# KGGRdac.net
KiCad netlist of a schematic drawn in EAGLE
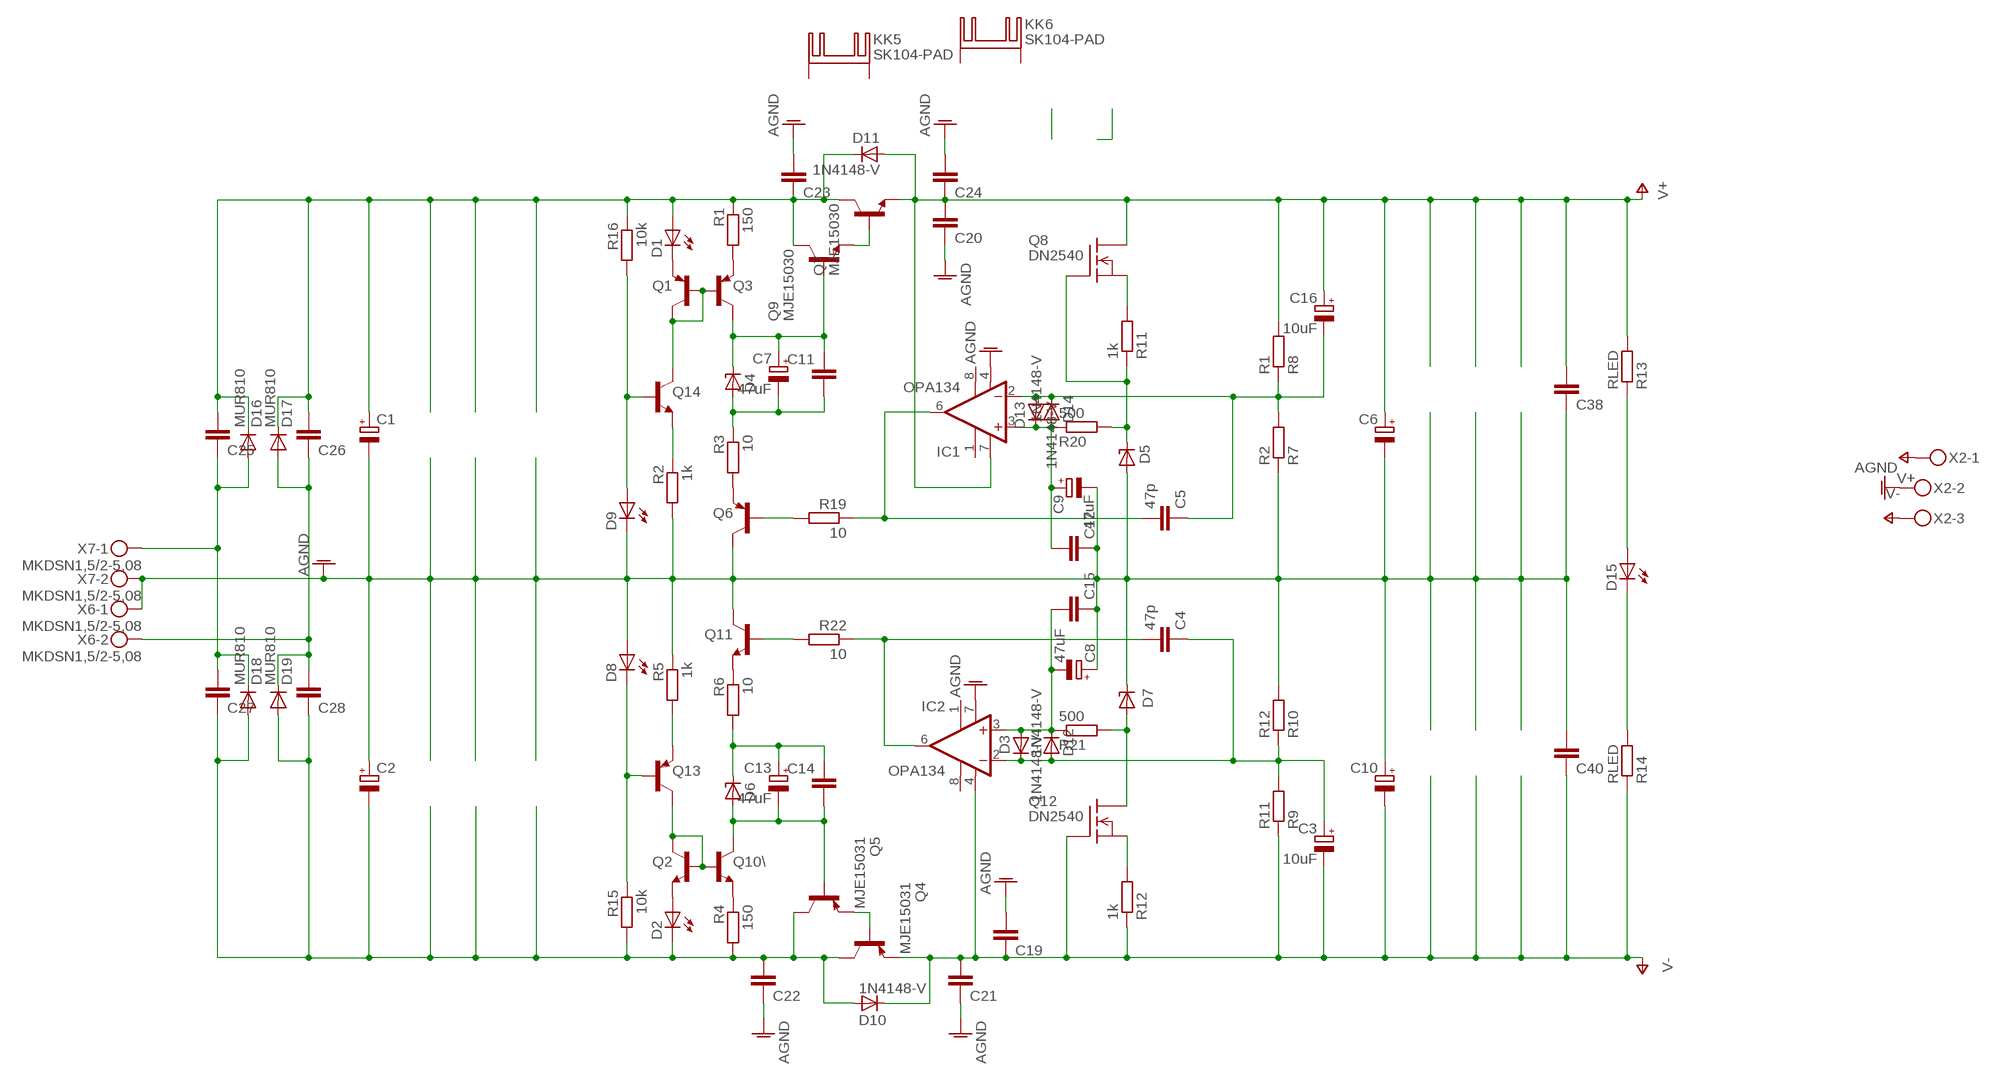
[diagram p0: schematic, sheet 1]
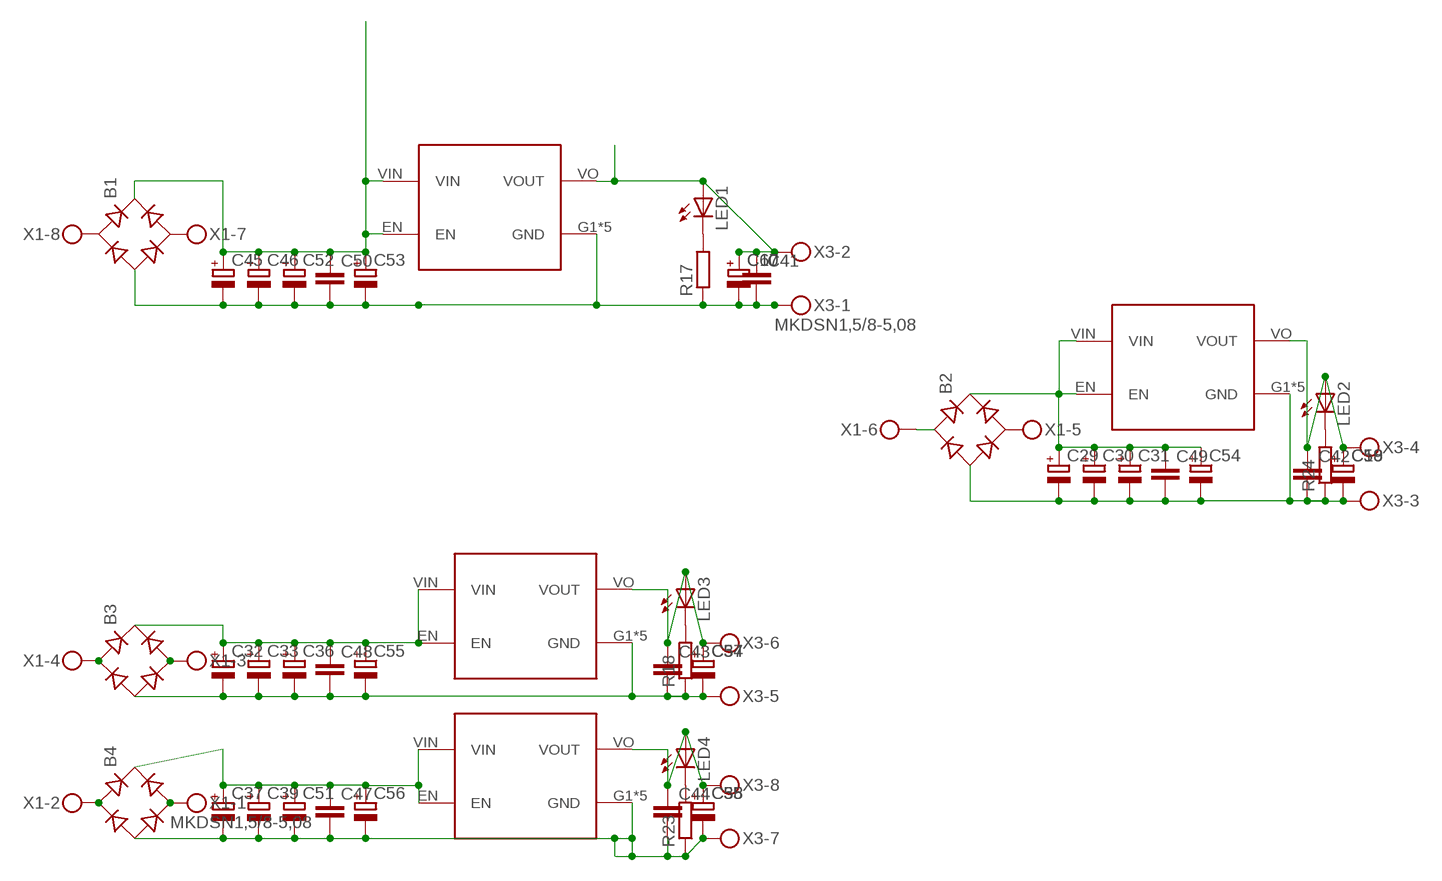
[diagram p1: schematic, sheet 2]
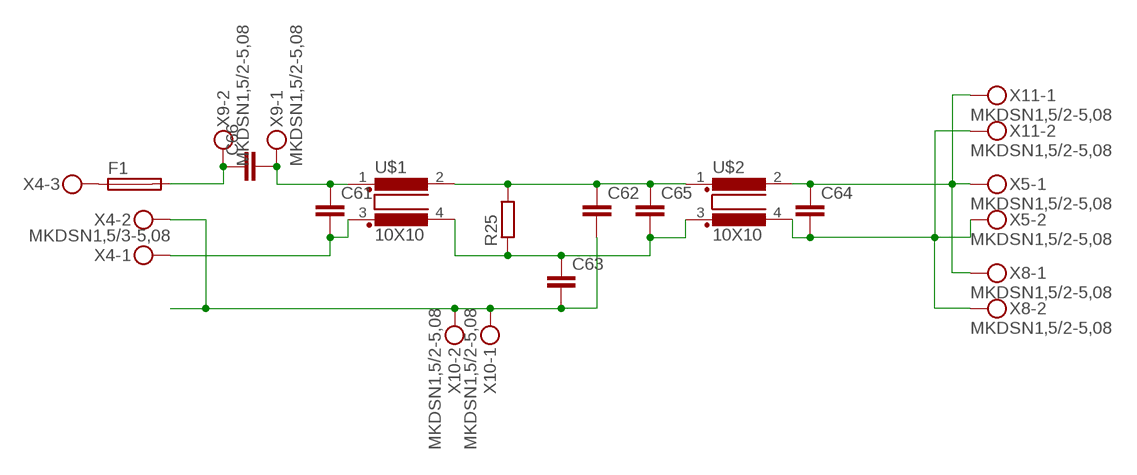
[diagram p2: schematic, sheet 3]

(export (version "E")
  (design (tool "Eeschema 10.0.6"))
  (components
    (comp (ref "C1")
      (value "CPOL-EUE10-35")
      (footprint "eagle-import:EB35D")
      (libsource (lib "eagle-import") (part "CPOL-EUE10-35"))
    )
    (comp (ref "C2")
      (value "CPOL-EUE10-35")
      (footprint "eagle-import:EB35D")
      (libsource (lib "eagle-import") (part "CPOL-EUE10-35"))
    )
    (comp (ref "C3")
      (value "10uF")
      (footprint "eagle-import:SP-CAP-CX")
      (libsource (lib "eagle-import") (part "CPOL-EUSP-CAP-CX"))
    )
    (comp (ref "C4")
      (value "47p")
      (footprint "eagle-import:C1206")
      (libsource (lib "eagle-import") (part "C-EUC1206"))
    )
    (comp (ref "C5")
      (value "47p")
      (footprint "eagle-import:C1206")
      (libsource (lib "eagle-import") (part "C-EUC1206"))
    )
    (comp (ref "C6")
      (value "CPOL-EUE5-13")
      (footprint "eagle-import:E5-13")
      (libsource (lib "eagle-import") (part "CPOL-EUE5-13"))
    )
    (comp (ref "C7")
      (value "47uF")
      (footprint "eagle-import:SP-CAP-CX")
      (libsource (lib "eagle-import") (part "CPOL-EUSP-CAP-CX"))
    )
    (comp (ref "C8")
      (value "47uF")
      (footprint "eagle-import:SP-CAP-CX")
      (libsource (lib "eagle-import") (part "CPOL-EUSP-CAP-CX"))
    )
    (comp (ref "C9")
      (value "47uF")
      (footprint "eagle-import:SP-CAP-CX")
      (libsource (lib "eagle-import") (part "CPOL-EUSP-CAP-CX"))
    )
    (comp (ref "C10")
      (value "CPOL-EUE5-13")
      (footprint "eagle-import:E5-13")
      (libsource (lib "eagle-import") (part "CPOL-EUE5-13"))
    )
    (comp (ref "C11")
      (value "C-EUC1206")
      (footprint "eagle-import:C1206")
      (libsource (lib "eagle-import") (part "C-EUC1206"))
    )
    (comp (ref "C12")
      (value "C-EU050-035X075")
      (footprint "eagle-import:C050-035X075")
      (libsource (lib "eagle-import") (part "C-EU050-035X075"))
    )
    (comp (ref "C13")
      (value "47uF")
      (footprint "eagle-import:SP-CAP-CX")
      (libsource (lib "eagle-import") (part "CPOL-EUSP-CAP-CX"))
    )
    (comp (ref "C14")
      (value "C-EUC1206")
      (footprint "eagle-import:C1206")
      (libsource (lib "eagle-import") (part "C-EUC1206"))
    )
    (comp (ref "C15")
      (value "C-EU050-035X075")
      (footprint "eagle-import:C050-035X075")
      (libsource (lib "eagle-import") (part "C-EU050-035X075"))
    )
    (comp (ref "C16")
      (value "10uF")
      (footprint "eagle-import:SP-CAP-CX")
      (libsource (lib "eagle-import") (part "CPOL-EUSP-CAP-CX"))
    )
    (comp (ref "C19")
      (value "C-EU050-035X075")
      (footprint "eagle-import:C050-035X075")
      (libsource (lib "eagle-import") (part "C-EU050-035X075"))
    )
    (comp (ref "C20")
      (value "C-EU050-035X075")
      (footprint "eagle-import:C050-035X075")
      (libsource (lib "eagle-import") (part "C-EU050-035X075"))
    )
    (comp (ref "C21")
      (value "C-EU050-035X075")
      (footprint "eagle-import:C050-035X075")
      (libsource (lib "eagle-import") (part "C-EU050-035X075"))
    )
    (comp (ref "C22")
      (value "C-EU050-075X075")
      (footprint "eagle-import:C050-075X075")
      (libsource (lib "eagle-import") (part "C-EU050-075X075"))
    )
    (comp (ref "C23")
      (value "C-EU050-075X075")
      (footprint "eagle-import:C050-075X075")
      (libsource (lib "eagle-import") (part "C-EU050-075X075"))
    )
    (comp (ref "C24")
      (value "C-EU050-035X075")
      (footprint "eagle-import:C050-035X075")
      (libsource (lib "eagle-import") (part "C-EU050-035X075"))
    )
    (comp (ref "C25")
      (value "C-EU050-035X075")
      (footprint "eagle-import:C050-035X075")
      (libsource (lib "eagle-import") (part "C-EU050-035X075"))
    )
    (comp (ref "C26")
      (value "C-EU050-035X075")
      (footprint "eagle-import:C050-035X075")
      (libsource (lib "eagle-import") (part "C-EU050-035X075"))
    )
    (comp (ref "C27")
      (value "C-EU050-035X075")
      (footprint "eagle-import:C050-035X075")
      (libsource (lib "eagle-import") (part "C-EU050-035X075"))
    )
    (comp (ref "C28")
      (value "C-EU050-035X075")
      (footprint "eagle-import:C050-035X075")
      (libsource (lib "eagle-import") (part "C-EU050-035X075"))
    )
    (comp (ref "C38")
      (value "C-EU050-035X075")
      (footprint "eagle-import:C050-035X075")
      (libsource (lib "eagle-import") (part "C-EU050-035X075"))
    )
    (comp (ref "C40")
      (value "C-EU050-035X075")
      (footprint "eagle-import:C050-035X075")
      (libsource (lib "eagle-import") (part "C-EU050-035X075"))
    )
    (comp (ref "D1")
      (value "LED5MM")
      (footprint "eagle-import:LED5MM")
      (libsource (lib "eagle-import") (part "LED5MM"))
    )
    (comp (ref "D2")
      (value "LED5MM")
      (footprint "eagle-import:LED5MM")
      (libsource (lib "eagle-import") (part "LED5MM"))
    )
    (comp (ref "D3")
      (value "1N4148-V")
      (footprint "eagle-import:1N4148")
      (libsource (lib "eagle-import") (part "1N4148-V"))
    )
    (comp (ref "D4")
      (value "1N4728")
      (footprint "eagle-import:DO41Z10")
      (libsource (lib "eagle-import") (part "1N4728"))
    )
    (comp (ref "D5")
      (value "LT1021")
      (footprint "eagle-import:DIL08")
      (libsource (lib "eagle-import") (part "LT1021-V"))
    )
    (comp (ref "D6")
      (value "1N4728")
      (footprint "eagle-import:DO41Z10")
      (libsource (lib "eagle-import") (part "1N4728"))
    )
    (comp (ref "D7")
      (value "LT1021")
      (footprint "eagle-import:DIL08")
      (libsource (lib "eagle-import") (part "LT1021-V"))
    )
    (comp (ref "D8")
      (value "LED5MM")
      (footprint "eagle-import:LED5MM")
      (libsource (lib "eagle-import") (part "LED5MM"))
    )
    (comp (ref "D9")
      (value "LED5MM")
      (footprint "eagle-import:LED5MM")
      (libsource (lib "eagle-import") (part "LED5MM"))
    )
    (comp (ref "D10")
      (value "1N4148-V")
      (footprint "eagle-import:1N4148")
      (libsource (lib "eagle-import") (part "1N4148-V"))
    )
    (comp (ref "D11")
      (value "1N4148-V")
      (footprint "eagle-import:1N4148")
      (libsource (lib "eagle-import") (part "1N4148-V"))
    )
    (comp (ref "D12")
      (value "1N4148-V")
      (footprint "eagle-import:1N4148")
      (libsource (lib "eagle-import") (part "1N4148-V"))
    )
    (comp (ref "D13")
      (value "1N4148-V")
      (footprint "eagle-import:1N4148")
      (libsource (lib "eagle-import") (part "1N4148-V"))
    )
    (comp (ref "D14")
      (value "1N4148-V")
      (footprint "eagle-import:1N4148")
      (libsource (lib "eagle-import") (part "1N4148-V"))
    )
    (comp (ref "D15")
      (value "LED5MM")
      (footprint "eagle-import:LED5MM")
      (libsource (lib "eagle-import") (part "LED5MM"))
    )
    (comp (ref "D16")
      (value "MUR810")
      (footprint "eagle-import:TO220ACS")
      (libsource (lib "eagle-import") (part "MUR810"))
    )
    (comp (ref "D17")
      (value "MUR810")
      (footprint "eagle-import:TO220ACS")
      (libsource (lib "eagle-import") (part "MUR810"))
    )
    (comp (ref "D18")
      (value "MUR810")
      (footprint "eagle-import:TO220ACS")
      (libsource (lib "eagle-import") (part "MUR810"))
    )
    (comp (ref "D19")
      (value "MUR810")
      (footprint "eagle-import:TO220ACS")
      (libsource (lib "eagle-import") (part "MUR810"))
    )
    (comp (ref "IC1")
      (value "OPA134")
      (footprint "eagle-import:DIL08")
      (fields (field (name "MF") "TEXAS INSTRUMENTS") (field (name "MPN") "OPA134PA"))
      (libsource (lib "eagle-import") (part "OPA134P"))
    )
    (comp (ref "IC2")
      (value "OPA134")
      (footprint "eagle-import:DIL08")
      (fields (field (name "MF") "TEXAS INSTRUMENTS") (field (name "MPN") "OPA134PA"))
      (libsource (lib "eagle-import") (part "OPA134P"))
    )
    (comp (ref "KK5")
      (value "SK104-PAD")
      (footprint "eagle-import:SK104-PAD")
      (libsource (lib "eagle-import") (part "SK104-PAD"))
    )
    (comp (ref "KK6")
      (value "SK104-PAD")
      (footprint "eagle-import:SK104-PAD")
      (libsource (lib "eagle-import") (part "SK104-PAD"))
    )
    (comp (ref "Q1")
      (value "MPSA92-PNP-TO92-EBC")
      (footprint "eagle-import:TO92-EBC")
      (libsource (lib "eagle-import") (part "-PNP-TO92-EBCMPSA92"))
    )
    (comp (ref "Q2")
      (value "MPSA42-NPN-TO92-EBC")
      (footprint "eagle-import:TO92-EBC")
      (libsource (lib "eagle-import") (part "-NPN-TO92-EBCMPSA42"))
    )
    (comp (ref "Q3")
      (value "MPSA92-PNP-TO92-EBC")
      (footprint "eagle-import:TO92-EBC")
      (libsource (lib "eagle-import") (part "-PNP-TO92-EBCMPSA92"))
    )
    (comp (ref "Q4")
      (value "MJE15031")
      (footprint "eagle-import:TO220KG")
      (libsource (lib "eagle-import") (part "MJE15031"))
    )
    (comp (ref "Q5")
      (value "MJE15031")
      (footprint "eagle-import:TO220KG")
      (libsource (lib "eagle-import") (part "MJE15031"))
    )
    (comp (ref "Q6")
      (value "MPSA92-PNP-TO92-EBC")
      (footprint "eagle-import:TO92-EBC")
      (libsource (lib "eagle-import") (part "-PNP-TO92-EBCMPSA92"))
    )
    (comp (ref "Q7")
      (value "MJE15030")
      (footprint "eagle-import:TO220KG")
      (libsource (lib "eagle-import") (part "MJE15030"))
    )
    (comp (ref "Q8")
      (value "DN2540")
      (footprint "eagle-import:TO92-")
      (libsource (lib "eagle-import") (part "2N7000TO92"))
    )
    (comp (ref "Q9")
      (value "MJE15030")
      (footprint "eagle-import:TO220KG")
      (libsource (lib "eagle-import") (part "MJE15030"))
    )
    (comp (ref "Q10\\")
      (value "MPSA42-NPN-TO92-EBC")
      (footprint "eagle-import:TO92-EBC")
      (libsource (lib "eagle-import") (part "-NPN-TO92-EBCMPSA42"))
    )
    (comp (ref "Q11")
      (value "MPSA42-NPN-TO92-EBC")
      (footprint "eagle-import:TO92-EBC")
      (libsource (lib "eagle-import") (part "-NPN-TO92-EBCMPSA42"))
    )
    (comp (ref "Q12")
      (value "DN2540")
      (footprint "eagle-import:TO92-")
      (libsource (lib "eagle-import") (part "2N7000TO92"))
    )
    (comp (ref "Q13")
      (value "MPSA92-PNP-TO92-EBC")
      (footprint "eagle-import:TO92-EBC")
      (libsource (lib "eagle-import") (part "-PNP-TO92-EBCMPSA92"))
    )
    (comp (ref "Q14")
      (value "MPSA42-NPN-TO92-EBC")
      (footprint "eagle-import:TO92-EBC")
      (libsource (lib "eagle-import") (part "-NPN-TO92-EBCMPSA42"))
    )
    (comp (ref "R1")
      (value "150")
      (footprint "eagle-import:0207_2V")
      (libsource (lib "eagle-import") (part "R-EU_0207/2V"))
    )
    (comp (ref "R2")
      (value "1k")
      (footprint "eagle-import:0207_2V")
      (libsource (lib "eagle-import") (part "R-EU_0207/2V"))
    )
    (comp (ref "R3")
      (value "10")
      (footprint "eagle-import:0207_2V")
      (libsource (lib "eagle-import") (part "R-EU_0207/2V"))
    )
    (comp (ref "R4")
      (value "150")
      (footprint "eagle-import:0207_2V")
      (libsource (lib "eagle-import") (part "R-EU_0207/2V"))
    )
    (comp (ref "R5")
      (value "1k")
      (footprint "eagle-import:0207_2V")
      (libsource (lib "eagle-import") (part "R-EU_0207/2V"))
    )
    (comp (ref "R6")
      (value "10")
      (footprint "eagle-import:0207_2V")
      (libsource (lib "eagle-import") (part "R-EU_0207/2V"))
    )
    (comp (ref "R7")
      (value "R2")
      (footprint "eagle-import:0207_2V")
      (libsource (lib "eagle-import") (part "R-EU_0207/2V"))
    )
    (comp (ref "R8")
      (value "R1")
      (footprint "eagle-import:0207_2V")
      (libsource (lib "eagle-import") (part "R-EU_0207/2V"))
    )
    (comp (ref "R9")
      (value "R11")
      (footprint "eagle-import:0207_2V")
      (libsource (lib "eagle-import") (part "R-EU_0207/2V"))
    )
    (comp (ref "R10")
      (value "R12")
      (footprint "eagle-import:0207_2V")
      (libsource (lib "eagle-import") (part "R-EU_0207/2V"))
    )
    (comp (ref "R11")
      (value "1k")
      (footprint "eagle-import:0207_2V")
      (libsource (lib "eagle-import") (part "R-EU_0207/2V"))
    )
    (comp (ref "R12")
      (value "1k")
      (footprint "eagle-import:0207_2V")
      (libsource (lib "eagle-import") (part "R-EU_0207/2V"))
    )
    (comp (ref "R13")
      (value "RLED")
      (footprint "eagle-import:0207_2V")
      (libsource (lib "eagle-import") (part "R-EU_0207/2V"))
    )
    (comp (ref "R14")
      (value "RLED")
      (footprint "eagle-import:0207_2V")
      (libsource (lib "eagle-import") (part "R-EU_0207/2V"))
    )
    (comp (ref "R15")
      (value "10k")
      (footprint "eagle-import:0207_2V")
      (libsource (lib "eagle-import") (part "R-EU_0207/2V"))
    )
    (comp (ref "R16")
      (value "10k")
      (footprint "eagle-import:0207_2V")
      (libsource (lib "eagle-import") (part "R-EU_0207/2V"))
    )
    (comp (ref "R19")
      (value "10")
      (footprint "eagle-import:0207_2V")
      (libsource (lib "eagle-import") (part "R-EU_0207/2V"))
    )
    (comp (ref "R20")
      (value "500")
      (footprint "eagle-import:0207_2V")
      (libsource (lib "eagle-import") (part "R-EU_0207/2V"))
    )
    (comp (ref "R21")
      (value "500")
      (footprint "eagle-import:0207_2V")
      (libsource (lib "eagle-import") (part "R-EU_0207/2V"))
    )
    (comp (ref "R22")
      (value "10")
      (footprint "eagle-import:0207_2V")
      (libsource (lib "eagle-import") (part "R-EU_0207/2V"))
    )
    (comp (ref "X2")
      (value "MKDSN1,5/3-5,08")
      (footprint "eagle-import:MKDSN1,5_3-5,08")
      (libsource (lib "eagle-import") (part "MKDSN1,5/3-5,08"))
    )
    (comp (ref "X6")
      (value "MKDSN1,5/2-5,08")
      (footprint "eagle-import:MKDSN1,5_2-5,08")
      (libsource (lib "eagle-import") (part "MKDSN1,5/2-5,08"))
    )
    (comp (ref "X7")
      (value "MKDSN1,5/2-5,08")
      (footprint "eagle-import:MKDSN1,5_2-5,08")
      (libsource (lib "eagle-import") (part "MKDSN1,5/2-5,08"))
    )
    (comp (ref "B1")
      (value "RB1A")
      (footprint "eagle-import:RB1A")
      (libsource (lib "eagle-import") (part "RB1A"))
    )
    (comp (ref "B2")
      (value "RB1A")
      (footprint "eagle-import:RB1A")
      (libsource (lib "eagle-import") (part "RB1A"))
    )
    (comp (ref "B3")
      (value "RB1A")
      (footprint "eagle-import:RB1A")
      (libsource (lib "eagle-import") (part "RB1A"))
    )
    (comp (ref "B4")
      (value "RB1A")
      (footprint "eagle-import:RB1A")
      (libsource (lib "eagle-import") (part "RB1A"))
    )
    (comp (ref "C17")
      (value "CPOL-EUSP-CAP-CX")
      (footprint "eagle-import:SP-CAP-CX")
      (libsource (lib "eagle-import") (part "CPOL-EUSP-CAP-CX"))
    )
    (comp (ref "C18")
      (value "CPOL-EUSP-CAP-CX")
      (footprint "eagle-import:SP-CAP-CX")
      (libsource (lib "eagle-import") (part "CPOL-EUSP-CAP-CX"))
    )
    (comp (ref "C29")
      (value "CPOL-EUSP-CAP-CX")
      (footprint "eagle-import:SP-CAP-CX")
      (libsource (lib "eagle-import") (part "CPOL-EUSP-CAP-CX"))
    )
    (comp (ref "C30")
      (value "CPOL-EUSP-CAP-CX")
      (footprint "eagle-import:SP-CAP-CX")
      (libsource (lib "eagle-import") (part "CPOL-EUSP-CAP-CX"))
    )
    (comp (ref "C31")
      (value "CPOL-EUSP-CAP-CX")
      (footprint "eagle-import:SP-CAP-CX")
      (libsource (lib "eagle-import") (part "CPOL-EUSP-CAP-CX"))
    )
    (comp (ref "C32")
      (value "CPOL-EUSP-CAP-CX")
      (footprint "eagle-import:SP-CAP-CX")
      (libsource (lib "eagle-import") (part "CPOL-EUSP-CAP-CX"))
    )
    (comp (ref "C33")
      (value "CPOL-EUSP-CAP-CX")
      (footprint "eagle-import:SP-CAP-CX")
      (libsource (lib "eagle-import") (part "CPOL-EUSP-CAP-CX"))
    )
    (comp (ref "C34")
      (value "CPOL-EUSP-CAP-CX")
      (footprint "eagle-import:SP-CAP-CX")
      (libsource (lib "eagle-import") (part "CPOL-EUSP-CAP-CX"))
    )
    (comp (ref "C35")
      (value "CPOL-EUSP-CAP-CX")
      (footprint "eagle-import:SP-CAP-CX")
      (libsource (lib "eagle-import") (part "CPOL-EUSP-CAP-CX"))
    )
    (comp (ref "C36")
      (value "CPOL-EUSP-CAP-CX")
      (footprint "eagle-import:SP-CAP-CX")
      (libsource (lib "eagle-import") (part "CPOL-EUSP-CAP-CX"))
    )
    (comp (ref "C37")
      (value "CPOL-EUSP-CAP-CX")
      (footprint "eagle-import:SP-CAP-CX")
      (libsource (lib "eagle-import") (part "CPOL-EUSP-CAP-CX"))
    )
    (comp (ref "C39")
      (value "CPOL-EUSP-CAP-CX")
      (footprint "eagle-import:SP-CAP-CX")
      (libsource (lib "eagle-import") (part "CPOL-EUSP-CAP-CX"))
    )
    (comp (ref "C41")
      (value "C-EUC1206")
      (footprint "eagle-import:C1206")
      (libsource (lib "eagle-import") (part "C-EUC1206"))
    )
    (comp (ref "C42")
      (value "C-EUC1206")
      (footprint "eagle-import:C1206")
      (libsource (lib "eagle-import") (part "C-EUC1206"))
    )
    (comp (ref "C43")
      (value "C-EUC1206")
      (footprint "eagle-import:C1206")
      (libsource (lib "eagle-import") (part "C-EUC1206"))
    )
    (comp (ref "C44")
      (value "C-EUC1206")
      (footprint "eagle-import:C1206")
      (libsource (lib "eagle-import") (part "C-EUC1206"))
    )
    (comp (ref "C45")
      (value "CPOL-EUSP-CAP-CX")
      (footprint "eagle-import:SP-CAP-CX")
      (libsource (lib "eagle-import") (part "CPOL-EUSP-CAP-CX"))
    )
    (comp (ref "C46")
      (value "CPOL-EUSP-CAP-CX")
      (footprint "eagle-import:SP-CAP-CX")
      (libsource (lib "eagle-import") (part "CPOL-EUSP-CAP-CX"))
    )
    (comp (ref "C47")
      (value "C-EUC1206")
      (footprint "eagle-import:C1206")
      (libsource (lib "eagle-import") (part "C-EUC1206"))
    )
    (comp (ref "C48")
      (value "C-EUC1206")
      (footprint "eagle-import:C1206")
      (libsource (lib "eagle-import") (part "C-EUC1206"))
    )
    (comp (ref "C49")
      (value "C-EUC1206")
      (footprint "eagle-import:C1206")
      (libsource (lib "eagle-import") (part "C-EUC1206"))
    )
    (comp (ref "C50")
      (value "C-EUC1206")
      (footprint "eagle-import:C1206")
      (libsource (lib "eagle-import") (part "C-EUC1206"))
    )
    (comp (ref "C51")
      (value "CPOL-EUSP-CAP-CX")
      (footprint "eagle-import:SP-CAP-CX")
      (libsource (lib "eagle-import") (part "CPOL-EUSP-CAP-CX"))
    )
    (comp (ref "C52")
      (value "CPOL-EUSP-CAP-CX")
      (footprint "eagle-import:SP-CAP-CX")
      (libsource (lib "eagle-import") (part "CPOL-EUSP-CAP-CX"))
    )
    (comp (ref "C53")
      (value "CPOL-EUSP-CAP-CX")
      (footprint "eagle-import:SP-CAP-CX")
      (libsource (lib "eagle-import") (part "CPOL-EUSP-CAP-CX"))
    )
    (comp (ref "C54")
      (value "CPOL-EUSP-CAP-CX")
      (footprint "eagle-import:SP-CAP-CX")
      (libsource (lib "eagle-import") (part "CPOL-EUSP-CAP-CX"))
    )
    (comp (ref "C55")
      (value "CPOL-EUSP-CAP-CX")
      (footprint "eagle-import:SP-CAP-CX")
      (libsource (lib "eagle-import") (part "CPOL-EUSP-CAP-CX"))
    )
    (comp (ref "C56")
      (value "CPOL-EUSP-CAP-CX")
      (footprint "eagle-import:SP-CAP-CX")
      (libsource (lib "eagle-import") (part "CPOL-EUSP-CAP-CX"))
    )
    (comp (ref "C57")
      (value "CPOL-EUSP-CAP-CX")
      (footprint "eagle-import:SP-CAP-CX")
      (libsource (lib "eagle-import") (part "CPOL-EUSP-CAP-CX"))
    )
    (comp (ref "C58")
      (value "CPOL-EUSP-CAP-CX")
      (footprint "eagle-import:SP-CAP-CX")
      (libsource (lib "eagle-import") (part "CPOL-EUSP-CAP-CX"))
    )
    (comp (ref "C59")
      (value "CPOL-EUSP-CAP-CX")
      (footprint "eagle-import:SP-CAP-CX")
      (libsource (lib "eagle-import") (part "CPOL-EUSP-CAP-CX"))
    )
    (comp (ref "C60")
      (value "CPOL-EUSP-CAP-CX")
      (footprint "eagle-import:SP-CAP-CX")
      (libsource (lib "eagle-import") (part "CPOL-EUSP-CAP-CX"))
    )
    (comp (ref "LED1")
      (value "LEDSML0805")
      (footprint "eagle-import:SML0805")
      (libsource (lib "eagle-import") (part "LEDSML0805"))
    )
    (comp (ref "LED2")
      (value "LEDSML0805")
      (footprint "eagle-import:SML0805")
      (libsource (lib "eagle-import") (part "LEDSML0805"))
    )
    (comp (ref "LED3")
      (value "LEDSML0805")
      (footprint "eagle-import:SML0805")
      (libsource (lib "eagle-import") (part "LEDSML0805"))
    )
    (comp (ref "LED4")
      (value "LEDSML0805")
      (footprint "eagle-import:SML0805")
      (libsource (lib "eagle-import") (part "LEDSML0805"))
    )
    (comp (ref "R17")
      (value "R-EU_MELF0204W")
      (footprint "eagle-import:MINI_MELF-0204W")
      (libsource (lib "eagle-import") (part "R-EU_MELF0204W"))
    )
    (comp (ref "R18")
      (value "R-EU_MELF0204W")
      (footprint "eagle-import:MINI_MELF-0204W")
      (libsource (lib "eagle-import") (part "R-EU_MELF0204W"))
    )
    (comp (ref "R23")
      (value "R-EU_MELF0204W")
      (footprint "eagle-import:MINI_MELF-0204W")
      (libsource (lib "eagle-import") (part "R-EU_MELF0204W"))
    )
    (comp (ref "R24")
      (value "R-EU_MELF0204W")
      (footprint "eagle-import:MINI_MELF-0204W")
      (libsource (lib "eagle-import") (part "R-EU_MELF0204W"))
    )
    (comp (ref "U$3")
      (value "POWER-MO")
      (footprint "eagle-import:POWER-MO")
      (libsource (lib "eagle-import") (part "POWER-MO"))
    )
    (comp (ref "U$4")
      (value "POWER-MO")
      (footprint "eagle-import:POWER-MO")
      (libsource (lib "eagle-import") (part "POWER-MO"))
    )
    (comp (ref "U$5")
      (value "POWER-MO")
      (footprint "eagle-import:POWER-MO")
      (libsource (lib "eagle-import") (part "POWER-MO"))
    )
    (comp (ref "U$6")
      (value "POWER-MO")
      (footprint "eagle-import:POWER-MO")
      (libsource (lib "eagle-import") (part "POWER-MO"))
    )
    (comp (ref "X1")
      (value "MKDSN1,5/8-5,08")
      (footprint "eagle-import:MKDSN1,5_8-5,08")
      (libsource (lib "eagle-import") (part "MKDSN1,5/8-5,08"))
    )
    (comp (ref "X3")
      (value "MKDSN1,5/8-5,08")
      (footprint "eagle-import:MKDSN1,5_8-5,08")
      (libsource (lib "eagle-import") (part "MKDSN1,5/8-5,08"))
    )
    (comp (ref "C61")
      (value "C-EU225-087X268")
      (footprint "eagle-import:C225-087X268")
      (libsource (lib "eagle-import") (part "C-EU225-087X268"))
    )
    (comp (ref "C62")
      (value "C-EU102-054X133")
      (footprint "eagle-import:C102-054X133")
      (libsource (lib "eagle-import") (part "C-EU102-054X133"))
    )
    (comp (ref "C63")
      (value "C-EU102-054X133")
      (footprint "eagle-import:C102-054X133")
      (libsource (lib "eagle-import") (part "C-EU102-054X133"))
    )
    (comp (ref "C64")
      (value "C-EU225-087X268")
      (footprint "eagle-import:C225-087X268")
      (libsource (lib "eagle-import") (part "C-EU225-087X268"))
    )
    (comp (ref "C65")
      (value "C-EU225-087X268")
      (footprint "eagle-import:C225-087X268")
      (libsource (lib "eagle-import") (part "C-EU225-087X268"))
    )
    (comp (ref "C66")
      (value "C-EU075-042X103")
      (footprint "eagle-import:C075-042X103")
      (libsource (lib "eagle-import") (part "C-EU075-042X103"))
    )
    (comp (ref "F1")
      (value "SH22,5A")
      (footprint "eagle-import:SH22,5A")
      (fields (field (name "MPN") "0031.7701.11"))
      (libsource (lib "eagle-import") (part "SH22,5A"))
    )
    (comp (ref "R25")
      (value "R-EU_0411/15")
      (footprint "eagle-import:0411_15")
      (libsource (lib "eagle-import") (part "R-EU_0411/15"))
    )
    (comp (ref "U$1")
      (value "10X10")
      (footprint "eagle-import:10X10")
      (libsource (lib "eagle-import") (part "10X10"))
    )
    (comp (ref "U$2")
      (value "10X10")
      (footprint "eagle-import:10X10")
      (libsource (lib "eagle-import") (part "10X10"))
    )
    (comp (ref "X4")
      (value "MKDSN1,5/3-5,08")
      (footprint "eagle-import:MKDSN1,5_3-5,08")
      (libsource (lib "eagle-import") (part "MKDSN1,5/3-5,08"))
    )
    (comp (ref "X5")
      (value "MKDSN1,5/2-5,08")
      (footprint "eagle-import:MKDSN1,5_2-5,08")
      (libsource (lib "eagle-import") (part "MKDSN1,5/2-5,08"))
    )
    (comp (ref "X8")
      (value "MKDSN1,5/2-5,08")
      (footprint "eagle-import:MKDSN1,5_2-5,08")
      (libsource (lib "eagle-import") (part "MKDSN1,5/2-5,08"))
    )
    (comp (ref "X9")
      (value "MKDSN1,5/2-5,08")
      (footprint "eagle-import:MKDSN1,5_2-5,08")
      (libsource (lib "eagle-import") (part "MKDSN1,5/2-5,08"))
    )
    (comp (ref "X10")
      (value "MKDSN1,5/2-5,08")
      (footprint "eagle-import:MKDSN1,5_2-5,08")
      (libsource (lib "eagle-import") (part "MKDSN1,5/2-5,08"))
    )
    (comp (ref "X11")
      (value "MKDSN1,5/2-5,08")
      (footprint "eagle-import:MKDSN1,5_2-5,08")
      (libsource (lib "eagle-import") (part "MKDSN1,5/2-5,08"))
    )
  )
  (nets
    (net (code "1") (name "AGND") (class "Default")
      (node (ref "C1") (pin "-") (pinfunction "-_-") (pintype "passive"))
      (node (ref "C10") (pin "+") (pinfunction "+_+") (pintype "passive"))
      (node (ref "C12") (pin "1") (pinfunction "1_1") (pintype "passive"))
      (node (ref "C15") (pin "1") (pinfunction "1_1") (pintype "passive"))
      (node (ref "C19") (pin "2") (pinfunction "2_2") (pintype "passive"))
      (node (ref "C2") (pin "+") (pinfunction "+_+") (pintype "passive"))
      (node (ref "C20") (pin "1") (pinfunction "1_1") (pintype "passive"))
      (node (ref "C21") (pin "1") (pinfunction "1_1") (pintype "passive"))
      (node (ref "C22") (pin "1") (pinfunction "1_1") (pintype "passive"))
      (node (ref "C23") (pin "2") (pinfunction "2_2") (pintype "passive"))
      (node (ref "C24") (pin "2") (pinfunction "2_2") (pintype "passive"))
      (node (ref "C38") (pin "1") (pinfunction "1_1") (pintype "passive"))
      (node (ref "C40") (pin "2") (pinfunction "2_2") (pintype "passive"))
      (node (ref "C6") (pin "-") (pinfunction "-_-") (pintype "passive"))
      (node (ref "C8") (pin "+") (pinfunction "+_+") (pintype "passive"))
      (node (ref "C9") (pin "-") (pinfunction "-_-") (pintype "passive"))
      (node (ref "D5") (pin "4") (pinfunction "GND_4") (pintype "passive"))
      (node (ref "D7") (pin "6") (pinfunction "OUT_6") (pintype "passive"))
      (node (ref "D8") (pin "A") (pinfunction "A_A") (pintype "passive"))
      (node (ref "D9") (pin "K") (pinfunction "C_K") (pintype "passive"))
      (node (ref "IC1") (pin "4") (pinfunction "V-_4") (pintype "power_in"))
      (node (ref "IC2") (pin "7") (pinfunction "V+_7") (pintype "power_in"))
      (node (ref "Q11") (pin "C") (pinfunction "C_C") (pintype "passive"))
      (node (ref "Q6") (pin "C") (pinfunction "C_C") (pintype "passive"))
      (node (ref "R10") (pin "2") (pinfunction "2_2") (pintype "passive"))
      (node (ref "R2") (pin "2") (pinfunction "2_2") (pintype "passive"))
      (node (ref "R5") (pin "1") (pinfunction "1_1") (pintype "passive"))
      (node (ref "R7") (pin "1") (pinfunction "1_1") (pintype "passive"))
      (node (ref "X2") (pin "2") (pinfunction "KL_2") (pintype "passive"))
      (node (ref "X6") (pin "1") (pinfunction "KL_1") (pintype "passive"))
      (node (ref "X7") (pin "2") (pinfunction "KL_2") (pintype "passive"))
    )
    (net (code "2") (name "Net-(B1-Pad+)") (class "Default")
      (node (ref "B1") (pin "+") (pinfunction "+_+") (pintype "passive"))
      (node (ref "C45") (pin "+") (pinfunction "+_+") (pintype "passive"))
      (node (ref "C46") (pin "+") (pinfunction "+_+") (pintype "passive"))
      (node (ref "C50") (pin "1") (pinfunction "1_1") (pintype "passive"))
      (node (ref "C52") (pin "+") (pinfunction "+_+") (pintype "passive"))
      (node (ref "C53") (pin "+") (pinfunction "+_+") (pintype "passive"))
      (node (ref "U$4") (pin "EN") (pinfunction "EN_EN") (pintype "bidirectional"))
      (node (ref "U$4") (pin "VIN") (pinfunction "VIN_VIN") (pintype "bidirectional"))
    )
    (net (code "3") (name "Net-(B2-Pad+)") (class "Default")
      (node (ref "B2") (pin "+") (pinfunction "+_+") (pintype "passive"))
      (node (ref "C29") (pin "+") (pinfunction "+_+") (pintype "passive"))
      (node (ref "C30") (pin "+") (pinfunction "+_+") (pintype "passive"))
      (node (ref "C31") (pin "+") (pinfunction "+_+") (pintype "passive"))
      (node (ref "C49") (pin "1") (pinfunction "1_1") (pintype "passive"))
      (node (ref "C54") (pin "+") (pinfunction "+_+") (pintype "passive"))
      (node (ref "U$3") (pin "EN") (pinfunction "EN_EN") (pintype "bidirectional"))
      (node (ref "U$3") (pin "VIN") (pinfunction "VIN_VIN") (pintype "bidirectional"))
    )
    (net (code "4") (name "Net-(B3-Pad+)") (class "Default")
      (node (ref "B3") (pin "+") (pinfunction "+_+") (pintype "passive"))
      (node (ref "C32") (pin "+") (pinfunction "+_+") (pintype "passive"))
      (node (ref "C33") (pin "+") (pinfunction "+_+") (pintype "passive"))
      (node (ref "C36") (pin "+") (pinfunction "+_+") (pintype "passive"))
      (node (ref "C48") (pin "1") (pinfunction "1_1") (pintype "passive"))
      (node (ref "C55") (pin "+") (pinfunction "+_+") (pintype "passive"))
      (node (ref "U$5") (pin "EN") (pinfunction "EN_EN") (pintype "bidirectional"))
      (node (ref "U$5") (pin "VIN") (pinfunction "VIN_VIN") (pintype "bidirectional"))
    )
    (net (code "5") (name "Net-(B4-Pad+)") (class "Default")
      (node (ref "B4") (pin "+") (pinfunction "+_+") (pintype "passive"))
      (node (ref "C37") (pin "+") (pinfunction "+_+") (pintype "passive"))
      (node (ref "C39") (pin "+") (pinfunction "+_+") (pintype "passive"))
      (node (ref "C47") (pin "1") (pinfunction "1_1") (pintype "passive"))
      (node (ref "C51") (pin "+") (pinfunction "+_+") (pintype "passive"))
      (node (ref "C56") (pin "+") (pinfunction "+_+") (pintype "passive"))
      (node (ref "U$6") (pin "EN") (pinfunction "EN_EN") (pintype "bidirectional"))
      (node (ref "U$6") (pin "VIN") (pinfunction "VIN_VIN") (pintype "bidirectional"))
    )
    (net (code "6") (name "Net-(C11-Pad2)") (class "Default")
      (node (ref "C11") (pin "2") (pinfunction "2_2") (pintype "passive"))
      (node (ref "C7") (pin "-") (pinfunction "-_-") (pintype "passive"))
      (node (ref "D4") (pin "A") (pinfunction "A_A") (pintype "passive"))
      (node (ref "R3") (pin "1") (pinfunction "1_1") (pintype "passive"))
    )
    (net (code "7") (name "Net-(C13-Pad+)") (class "Default")
      (node (ref "C13") (pin "+") (pinfunction "+_+") (pintype "passive"))
      (node (ref "C14") (pin "1") (pinfunction "1_1") (pintype "passive"))
      (node (ref "D6") (pin "C") (pinfunction "C_C") (pintype "passive"))
      (node (ref "R6") (pin "2") (pinfunction "2_2") (pintype "passive"))
    )
    (net (code "8") (name "Net-(C62-Pad1)") (class "Default")
      (node (ref "C62") (pin "1") (pinfunction "1_1") (pintype "passive"))
      (node (ref "C65") (pin "1") (pinfunction "1_1") (pintype "passive"))
      (node (ref "R25") (pin "2") (pinfunction "2_2") (pintype "passive"))
      (node (ref "U$1") (pin "2") (pinfunction "2_2") (pintype "passive"))
      (node (ref "U$2") (pin "1") (pinfunction "1_1") (pintype "passive"))
    )
    (net (code "9") (name "Net-(C63-Pad1)") (class "Default")
      (node (ref "C63") (pin "1") (pinfunction "1_1") (pintype "passive"))
      (node (ref "C65") (pin "2") (pinfunction "2_2") (pintype "passive"))
      (node (ref "R25") (pin "1") (pinfunction "1_1") (pintype "passive"))
      (node (ref "U$1") (pin "4") (pinfunction "4_4") (pintype "passive"))
      (node (ref "U$2") (pin "3") (pinfunction "3_3") (pintype "passive"))
    )
    (net (code "10") (name "Net-(D1-C)") (class "Default")
      (node (ref "D1") (pin "K") (pinfunction "C_K") (pintype "passive"))
      (node (ref "Q1") (pin "E") (pinfunction "E_E") (pintype "passive"))
    )
    (net (code "11") (name "Net-(D2-C)") (class "Default")
      (node (ref "C2") (pin "-") (pinfunction "-_-") (pintype "passive"))
      (node (ref "C22") (pin "2") (pinfunction "2_2") (pintype "passive"))
      (node (ref "C27") (pin "1") (pinfunction "1_1") (pintype "passive"))
      (node (ref "C28") (pin "1") (pinfunction "1_1") (pintype "passive"))
      (node (ref "D10") (pin "A") (pinfunction "A_A") (pintype "passive"))
      (node (ref "D18") (pin "A") (pinfunction "A_A") (pintype "passive"))
      (node (ref "D19") (pin "A") (pinfunction "A_A") (pintype "passive"))
      (node (ref "D2") (pin "K") (pinfunction "C_K") (pintype "passive"))
      (node (ref "Q4") (pin "2") (pinfunction "C_2") (pintype "passive"))
      (node (ref "Q5") (pin "2") (pinfunction "C_2") (pintype "passive"))
      (node (ref "R15") (pin "2") (pinfunction "2_2") (pintype "passive"))
      (node (ref "R4") (pin "2") (pinfunction "2_2") (pintype "passive"))
    )
    (net (code "12") (name "Net-(D2-PadA)") (class "Default")
      (node (ref "D2") (pin "A") (pinfunction "A_A") (pintype "passive"))
      (node (ref "Q2") (pin "E") (pinfunction "E_E") (pintype "passive"))
    )
    (net (code "13") (name "Net-(D5-OUT)") (class "Default")
      (node (ref "D5") (pin "6") (pinfunction "OUT_6") (pintype "passive"))
      (node (ref "Q8") (pin "2") (pinfunction "G_2") (pintype "passive"))
      (node (ref "R11") (pin "1") (pinfunction "1_1") (pintype "passive"))
      (node (ref "R20") (pin "2") (pinfunction "2_2") (pintype "passive"))
    )
    (net (code "14") (name "Net-(D7-GND)") (class "Default")
      (node (ref "D7") (pin "4") (pinfunction "GND_4") (pintype "passive"))
      (node (ref "Q12") (pin "1") (pinfunction "D_1") (pintype "passive"))
      (node (ref "R21") (pin "2") (pinfunction "2_2") (pintype "passive"))
    )
    (net (code "15") (name "Net-(D8-C)") (class "Default")
      (node (ref "D8") (pin "K") (pinfunction "C_K") (pintype "passive"))
      (node (ref "Q13") (pin "B") (pinfunction "B_B") (pintype "passive"))
      (node (ref "R15") (pin "1") (pinfunction "1_1") (pintype "passive"))
    )
    (net (code "16") (name "Net-(D9-PadA)") (class "Default")
      (node (ref "D9") (pin "A") (pinfunction "A_A") (pintype "passive"))
      (node (ref "Q14") (pin "B") (pinfunction "B_B") (pintype "passive"))
      (node (ref "R16") (pin "2") (pinfunction "2_2") (pintype "passive"))
    )
    (net (code "17") (name "Net-(D15-C)") (class "Default")
      (node (ref "D15") (pin "K") (pinfunction "C_K") (pintype "passive"))
      (node (ref "R14") (pin "2") (pinfunction "2_2") (pintype "passive"))
    )
    (net (code "18") (name "Net-(D15-PadA)") (class "Default")
      (node (ref "D15") (pin "A") (pinfunction "A_A") (pintype "passive"))
      (node (ref "R13") (pin "1") (pinfunction "1_1") (pintype "passive"))
    )
    (net (code "19") (name "Net-(IC1-+IN)") (class "Default")
      (node (ref "C12") (pin "2") (pinfunction "2_2") (pintype "passive"))
      (node (ref "C9") (pin "+") (pinfunction "+_+") (pintype "passive"))
      (node (ref "D13") (pin "C") (pinfunction "C_C") (pintype "passive"))
      (node (ref "D14") (pin "A") (pinfunction "A_A") (pintype "passive"))
      (node (ref "IC1") (pin "3") (pinfunction "+IN_3") (pintype "input"))
      (node (ref "R20") (pin "1") (pinfunction "1_1") (pintype "passive"))
    )
    (net (code "20") (name "Net-(IC1--IN)") (class "Default")
      (node (ref "C16") (pin "-") (pinfunction "-_-") (pintype "passive"))
      (node (ref "C5") (pin "1") (pinfunction "1_1") (pintype "passive"))
      (node (ref "D13") (pin "A") (pinfunction "A_A") (pintype "passive"))
      (node (ref "D14") (pin "C") (pinfunction "C_C") (pintype "passive"))
      (node (ref "IC1") (pin "2") (pinfunction "-IN_2") (pintype "input"))
      (node (ref "R7") (pin "2") (pinfunction "2_2") (pintype "passive"))
      (node (ref "R8") (pin "1") (pinfunction "1_1") (pintype "passive"))
    )
    (net (code "21") (name "Net-(IC1-OUT)") (class "Default")
      (node (ref "C5") (pin "2") (pinfunction "2_2") (pintype "passive"))
      (node (ref "IC1") (pin "6") (pinfunction "OUT_6") (pintype "output"))
      (node (ref "R19") (pin "1") (pinfunction "1_1") (pintype "passive"))
    )
    (net (code "22") (name "Net-(IC2-+IN)") (class "Default")
      (node (ref "C15") (pin "2") (pinfunction "2_2") (pintype "passive"))
      (node (ref "C8") (pin "-") (pinfunction "-_-") (pintype "passive"))
      (node (ref "D12") (pin "C") (pinfunction "C_C") (pintype "passive"))
      (node (ref "D3") (pin "A") (pinfunction "A_A") (pintype "passive"))
      (node (ref "IC2") (pin "3") (pinfunction "+IN_3") (pintype "input"))
      (node (ref "R21") (pin "1") (pinfunction "1_1") (pintype "passive"))
    )
    (net (code "23") (name "Net-(IC2--IN)") (class "Default")
      (node (ref "C3") (pin "+") (pinfunction "+_+") (pintype "passive"))
      (node (ref "C4") (pin "1") (pinfunction "1_1") (pintype "passive"))
      (node (ref "D12") (pin "A") (pinfunction "A_A") (pintype "passive"))
      (node (ref "D3") (pin "C") (pinfunction "C_C") (pintype "passive"))
      (node (ref "IC2") (pin "2") (pinfunction "-IN_2") (pintype "input"))
      (node (ref "R10") (pin "1") (pinfunction "1_1") (pintype "passive"))
      (node (ref "R9") (pin "2") (pinfunction "2_2") (pintype "passive"))
    )
    (net (code "24") (name "Net-(IC2-OUT)") (class "Default")
      (node (ref "C4") (pin "2") (pinfunction "2_2") (pintype "passive"))
      (node (ref "IC2") (pin "6") (pinfunction "OUT_6") (pintype "output"))
      (node (ref "R22") (pin "1") (pinfunction "1_1") (pintype "passive"))
    )
    (net (code "25") (name "Net-(LED1-PadC)") (class "Default")
      (node (ref "LED1") (pin "C") (pinfunction "C_C") (pintype "passive"))
      (node (ref "R17") (pin "2") (pinfunction "2_2") (pintype "passive"))
    )
    (net (code "26") (name "Net-(LED2-PadC)") (class "Default")
      (node (ref "LED2") (pin "C") (pinfunction "C_C") (pintype "passive"))
      (node (ref "R24") (pin "2") (pinfunction "2_2") (pintype "passive"))
    )
    (net (code "27") (name "Net-(LED3-PadC)") (class "Default")
      (node (ref "LED3") (pin "C") (pinfunction "C_C") (pintype "passive"))
      (node (ref "R18") (pin "2") (pinfunction "2_2") (pintype "passive"))
    )
    (net (code "28") (name "Net-(LED4-PadC)") (class "Default")
      (node (ref "LED4") (pin "C") (pinfunction "C_C") (pintype "passive"))
      (node (ref "R23") (pin "2") (pinfunction "2_2") (pintype "passive"))
    )
    (net (code "29") (name "Net-(Q1-PadB)") (class "Default")
      (node (ref "Q1") (pin "B") (pinfunction "B_B") (pintype "passive"))
      (node (ref "Q1") (pin "C") (pinfunction "C_C") (pintype "passive"))
      (node (ref "Q14") (pin "C") (pinfunction "C_C") (pintype "passive"))
      (node (ref "Q3") (pin "B") (pinfunction "B_B") (pintype "passive"))
    )
    (net (code "30") (name "Net-(Q3-PadE)") (class "Default")
      (node (ref "Q3") (pin "E") (pinfunction "E_E") (pintype "passive"))
      (node (ref "R1") (pin "2") (pinfunction "2_2") (pintype "passive"))
    )
    (net (code "31") (name "Net-(Q4-B)") (class "Default")
      (node (ref "Q4") (pin "1") (pinfunction "B_1") (pintype "passive"))
      (node (ref "Q5") (pin "3") (pinfunction "E_3") (pintype "passive"))
    )
    (net (code "32") (name "Net-(Q5-B)") (class "Default")
      (node (ref "C13") (pin "-") (pinfunction "-_-") (pintype "passive"))
      (node (ref "C14") (pin "2") (pinfunction "2_2") (pintype "passive"))
      (node (ref "D6") (pin "A") (pinfunction "A_A") (pintype "passive"))
      (node (ref "Q10\\") (pin "C") (pinfunction "C_C") (pintype "passive"))
      (node (ref "Q5") (pin "1") (pinfunction "B_1") (pintype "passive"))
    )
    (net (code "33") (name "Net-(Q6-PadB)") (class "Default")
      (node (ref "Q6") (pin "B") (pinfunction "B_B") (pintype "passive"))
      (node (ref "R19") (pin "2") (pinfunction "2_2") (pintype "passive"))
    )
    (net (code "34") (name "Net-(Q6-PadE)") (class "Default")
      (node (ref "Q6") (pin "E") (pinfunction "E_E") (pintype "passive"))
      (node (ref "R3") (pin "2") (pinfunction "2_2") (pintype "passive"))
    )
    (net (code "35") (name "Net-(Q7-B)") (class "Default")
      (node (ref "Q7") (pin "1") (pinfunction "B_1") (pintype "passive"))
      (node (ref "Q9") (pin "3") (pinfunction "E_3") (pintype "passive"))
    )
    (net (code "36") (name "Net-(Q7-C)") (class "Default")
      (node (ref "C1") (pin "+") (pinfunction "+_+") (pintype "passive"))
      (node (ref "C23") (pin "1") (pinfunction "1_1") (pintype "passive"))
      (node (ref "C25") (pin "2") (pinfunction "2_2") (pintype "passive"))
      (node (ref "C26") (pin "2") (pinfunction "2_2") (pintype "passive"))
      (node (ref "D1") (pin "A") (pinfunction "A_A") (pintype "passive"))
      (node (ref "D11") (pin "C") (pinfunction "C_C") (pintype "passive"))
      (node (ref "D16") (pin "C") (pinfunction "C_C") (pintype "passive"))
      (node (ref "D17") (pin "C") (pinfunction "C_C") (pintype "passive"))
      (node (ref "Q7") (pin "2") (pinfunction "C_2") (pintype "passive"))
      (node (ref "Q9") (pin "2") (pinfunction "C_2") (pintype "passive"))
      (node (ref "R1") (pin "1") (pinfunction "1_1") (pintype "passive"))
      (node (ref "R16") (pin "1") (pinfunction "1_1") (pintype "passive"))
    )
    (net (code "37") (name "Net-(Q8-S)") (class "Default")
      (node (ref "Q8") (pin "3") (pinfunction "S_3") (pintype "passive"))
      (node (ref "R11") (pin "2") (pinfunction "2_2") (pintype "passive"))
    )
    (net (code "38") (name "Net-(Q9-B)") (class "Default")
      (node (ref "C11") (pin "1") (pinfunction "1_1") (pintype "passive"))
      (node (ref "C7") (pin "+") (pinfunction "+_+") (pintype "passive"))
      (node (ref "D4") (pin "C") (pinfunction "C_C") (pintype "passive"))
      (node (ref "Q3") (pin "C") (pinfunction "C_C") (pintype "passive"))
      (node (ref "Q9") (pin "1") (pinfunction "B_1") (pintype "passive"))
    )
    (net (code "39") (name "Net-(Q10\\-PadB)") (class "Default")
      (node (ref "Q10\\") (pin "B") (pinfunction "B_B") (pintype "passive"))
      (node (ref "Q13") (pin "C") (pinfunction "C_C") (pintype "passive"))
      (node (ref "Q2") (pin "B") (pinfunction "B_B") (pintype "passive"))
      (node (ref "Q2") (pin "C") (pinfunction "C_C") (pintype "passive"))
    )
    (net (code "40") (name "Net-(Q10\\-PadE)") (class "Default")
      (node (ref "Q10\\") (pin "E") (pinfunction "E_E") (pintype "passive"))
      (node (ref "R4") (pin "1") (pinfunction "1_1") (pintype "passive"))
    )
    (net (code "41") (name "Net-(Q11-PadB)") (class "Default")
      (node (ref "Q11") (pin "B") (pinfunction "B_B") (pintype "passive"))
      (node (ref "R22") (pin "2") (pinfunction "2_2") (pintype "passive"))
    )
    (net (code "42") (name "Net-(Q11-PadE)") (class "Default")
      (node (ref "Q11") (pin "E") (pinfunction "E_E") (pintype "passive"))
      (node (ref "R6") (pin "1") (pinfunction "1_1") (pintype "passive"))
    )
    (net (code "43") (name "Net-(Q12-S)") (class "Default")
      (node (ref "Q12") (pin "3") (pinfunction "S_3") (pintype "passive"))
      (node (ref "R12") (pin "2") (pinfunction "2_2") (pintype "passive"))
    )
    (net (code "44") (name "Net-(Q13-PadE)") (class "Default")
      (node (ref "Q13") (pin "E") (pinfunction "E_E") (pintype "passive"))
      (node (ref "R5") (pin "2") (pinfunction "2_2") (pintype "passive"))
    )
    (net (code "45") (name "Net-(Q14-PadE)") (class "Default")
      (node (ref "Q14") (pin "E") (pinfunction "E_E") (pintype "passive"))
      (node (ref "R2") (pin "1") (pinfunction "1_1") (pintype "passive"))
    )
    (net (code "46") (name "Net-(U$3-VOUT)") (class "Default")
      (node (ref "C18") (pin "+") (pinfunction "+_+") (pintype "passive"))
      (node (ref "C42") (pin "1") (pinfunction "1_1") (pintype "passive"))
      (node (ref "C59") (pin "+") (pinfunction "+_+") (pintype "passive"))
      (node (ref "LED2") (pin "A") (pinfunction "A_A") (pintype "passive"))
      (node (ref "U$3") (pin "VO") (pinfunction "VOUT_VO") (pintype "bidirectional"))
      (node (ref "X3") (pin "4") (pinfunction "KL_4") (pintype "passive"))
    )
    (net (code "47") (name "Net-(U$4-VOUT)") (class "Default")
      (node (ref "C17") (pin "+") (pinfunction "+_+") (pintype "passive"))
      (node (ref "C41") (pin "1") (pinfunction "1_1") (pintype "passive"))
      (node (ref "C60") (pin "+") (pinfunction "+_+") (pintype "passive"))
      (node (ref "LED1") (pin "A") (pinfunction "A_A") (pintype "passive"))
      (node (ref "U$4") (pin "VO") (pinfunction "VOUT_VO") (pintype "bidirectional"))
      (node (ref "X3") (pin "2") (pinfunction "KL_2") (pintype "passive"))
    )
    (net (code "48") (name "Net-(U$5-VOUT)") (class "Default")
      (node (ref "C34") (pin "+") (pinfunction "+_+") (pintype "passive"))
      (node (ref "C43") (pin "1") (pinfunction "1_1") (pintype "passive"))
      (node (ref "C57") (pin "+") (pinfunction "+_+") (pintype "passive"))
      (node (ref "LED3") (pin "A") (pinfunction "A_A") (pintype "passive"))
      (node (ref "U$5") (pin "VO") (pinfunction "VOUT_VO") (pintype "bidirectional"))
      (node (ref "X3") (pin "6") (pinfunction "KL_6") (pintype "passive"))
    )
    (net (code "49") (name "Net-(U$6-VOUT)") (class "Default")
      (node (ref "C35") (pin "+") (pinfunction "+_+") (pintype "passive"))
      (node (ref "C44") (pin "1") (pinfunction "1_1") (pintype "passive"))
      (node (ref "C58") (pin "+") (pinfunction "+_+") (pintype "passive"))
      (node (ref "LED4") (pin "A") (pinfunction "A_A") (pintype "passive"))
      (node (ref "U$6") (pin "VO") (pinfunction "VOUT_VO") (pintype "bidirectional"))
      (node (ref "X3") (pin "8") (pinfunction "KL_8") (pintype "passive"))
    )
    (net (code "50") (name "Net-(X1A-KL)") (class "Default")
      (node (ref "B4") (pin "AC2") (pinfunction "AC2_AC2") (pintype "passive"))
      (node (ref "X1") (pin "1") (pinfunction "KL_1") (pintype "passive"))
    )
    (net (code "51") (name "Net-(X1B-KL)") (class "Default")
      (node (ref "B4") (pin "AC1") (pinfunction "AC1_AC1") (pintype "passive"))
      (node (ref "X1") (pin "2") (pinfunction "KL_2") (pintype "passive"))
    )
    (net (code "52") (name "Net-(X1C-KL)") (class "Default")
      (node (ref "B3") (pin "AC2") (pinfunction "AC2_AC2") (pintype "passive"))
      (node (ref "X1") (pin "3") (pinfunction "KL_3") (pintype "passive"))
    )
    (net (code "53") (name "Net-(X1D-KL)") (class "Default")
      (node (ref "B3") (pin "AC1") (pinfunction "AC1_AC1") (pintype "passive"))
      (node (ref "X1") (pin "4") (pinfunction "KL_4") (pintype "passive"))
    )
    (net (code "54") (name "Net-(X1E-KL)") (class "Default")
      (node (ref "B2") (pin "AC2") (pinfunction "AC2_AC2") (pintype "passive"))
      (node (ref "X1") (pin "5") (pinfunction "KL_5") (pintype "passive"))
    )
    (net (code "55") (name "Net-(X1F-KL)") (class "Default")
      (node (ref "B2") (pin "AC1") (pinfunction "AC1_AC1") (pintype "passive"))
      (node (ref "X1") (pin "6") (pinfunction "KL_6") (pintype "passive"))
    )
    (net (code "56") (name "Net-(X1G-KL)") (class "Default")
      (node (ref "B1") (pin "AC2") (pinfunction "AC2_AC2") (pintype "passive"))
      (node (ref "X1") (pin "7") (pinfunction "KL_7") (pintype "passive"))
    )
    (net (code "57") (name "Net-(X1H-KL)") (class "Default")
      (node (ref "B1") (pin "AC1") (pinfunction "AC1_AC1") (pintype "passive"))
      (node (ref "X1") (pin "8") (pinfunction "KL_8") (pintype "passive"))
    )
    (net (code "58") (name "Net-(X3A-KL)") (class "Default")
      (node (ref "B1") (pin "-") (pinfunction "-_-") (pintype "passive"))
      (node (ref "C17") (pin "-") (pinfunction "-_-") (pintype "passive"))
      (node (ref "C41") (pin "2") (pinfunction "2_2") (pintype "passive"))
      (node (ref "C45") (pin "-") (pinfunction "-_-") (pintype "passive"))
      (node (ref "C46") (pin "-") (pinfunction "-_-") (pintype "passive"))
      (node (ref "C50") (pin "2") (pinfunction "2_2") (pintype "passive"))
      (node (ref "C52") (pin "-") (pinfunction "-_-") (pintype "passive"))
      (node (ref "C53") (pin "-") (pinfunction "-_-") (pintype "passive"))
      (node (ref "C60") (pin "-") (pinfunction "-_-") (pintype "passive"))
      (node (ref "R17") (pin "1") (pinfunction "1_1") (pintype "passive"))
      (node (ref "U$4") (pin "G1") (pinfunction "GND_G1") (pintype "bidirectional"))
      (node (ref "U$4") (pin "G2") (pinfunction "GND_G2") (pintype "bidirectional"))
      (node (ref "U$4") (pin "G3") (pinfunction "GND_G3") (pintype "bidirectional"))
      (node (ref "U$4") (pin "G4") (pinfunction "GND_G4") (pintype "bidirectional"))
      (node (ref "U$4") (pin "G5") (pinfunction "GND_G5") (pintype "bidirectional"))
      (node (ref "X3") (pin "1") (pinfunction "KL_1") (pintype "passive"))
    )
    (net (code "59") (name "Net-(X3C-KL)") (class "Default")
      (node (ref "B2") (pin "-") (pinfunction "-_-") (pintype "passive"))
      (node (ref "C18") (pin "-") (pinfunction "-_-") (pintype "passive"))
      (node (ref "C29") (pin "-") (pinfunction "-_-") (pintype "passive"))
      (node (ref "C30") (pin "-") (pinfunction "-_-") (pintype "passive"))
      (node (ref "C31") (pin "-") (pinfunction "-_-") (pintype "passive"))
      (node (ref "C42") (pin "2") (pinfunction "2_2") (pintype "passive"))
      (node (ref "C49") (pin "2") (pinfunction "2_2") (pintype "passive"))
      (node (ref "C54") (pin "-") (pinfunction "-_-") (pintype "passive"))
      (node (ref "C59") (pin "-") (pinfunction "-_-") (pintype "passive"))
      (node (ref "R24") (pin "1") (pinfunction "1_1") (pintype "passive"))
      (node (ref "U$3") (pin "G1") (pinfunction "GND_G1") (pintype "bidirectional"))
      (node (ref "U$3") (pin "G2") (pinfunction "GND_G2") (pintype "bidirectional"))
      (node (ref "U$3") (pin "G3") (pinfunction "GND_G3") (pintype "bidirectional"))
      (node (ref "U$3") (pin "G4") (pinfunction "GND_G4") (pintype "bidirectional"))
      (node (ref "U$3") (pin "G5") (pinfunction "GND_G5") (pintype "bidirectional"))
      (node (ref "X3") (pin "3") (pinfunction "KL_3") (pintype "passive"))
    )
    (net (code "60") (name "Net-(X3E-KL)") (class "Default")
      (node (ref "B3") (pin "-") (pinfunction "-_-") (pintype "passive"))
      (node (ref "C32") (pin "-") (pinfunction "-_-") (pintype "passive"))
      (node (ref "C33") (pin "-") (pinfunction "-_-") (pintype "passive"))
      (node (ref "C34") (pin "-") (pinfunction "-_-") (pintype "passive"))
      (node (ref "C36") (pin "-") (pinfunction "-_-") (pintype "passive"))
      (node (ref "C43") (pin "2") (pinfunction "2_2") (pintype "passive"))
      (node (ref "C48") (pin "2") (pinfunction "2_2") (pintype "passive"))
      (node (ref "C55") (pin "-") (pinfunction "-_-") (pintype "passive"))
      (node (ref "C57") (pin "-") (pinfunction "-_-") (pintype "passive"))
      (node (ref "R18") (pin "1") (pinfunction "1_1") (pintype "passive"))
      (node (ref "U$5") (pin "G1") (pinfunction "GND_G1") (pintype "bidirectional"))
      (node (ref "U$5") (pin "G2") (pinfunction "GND_G2") (pintype "bidirectional"))
      (node (ref "U$5") (pin "G3") (pinfunction "GND_G3") (pintype "bidirectional"))
      (node (ref "U$5") (pin "G4") (pinfunction "GND_G4") (pintype "bidirectional"))
      (node (ref "U$5") (pin "G5") (pinfunction "GND_G5") (pintype "bidirectional"))
      (node (ref "X3") (pin "5") (pinfunction "KL_5") (pintype "passive"))
    )
    (net (code "61") (name "Net-(X3G-KL)") (class "Default")
      (node (ref "B4") (pin "-") (pinfunction "-_-") (pintype "passive"))
      (node (ref "C35") (pin "-") (pinfunction "-_-") (pintype "passive"))
      (node (ref "C37") (pin "-") (pinfunction "-_-") (pintype "passive"))
      (node (ref "C39") (pin "-") (pinfunction "-_-") (pintype "passive"))
      (node (ref "C44") (pin "2") (pinfunction "2_2") (pintype "passive"))
      (node (ref "C47") (pin "2") (pinfunction "2_2") (pintype "passive"))
      (node (ref "C51") (pin "-") (pinfunction "-_-") (pintype "passive"))
      (node (ref "C56") (pin "-") (pinfunction "-_-") (pintype "passive"))
      (node (ref "C58") (pin "-") (pinfunction "-_-") (pintype "passive"))
      (node (ref "R23") (pin "1") (pinfunction "1_1") (pintype "passive"))
      (node (ref "U$6") (pin "G1") (pinfunction "GND_G1") (pintype "bidirectional"))
      (node (ref "U$6") (pin "G2") (pinfunction "GND_G2") (pintype "bidirectional"))
      (node (ref "U$6") (pin "G3") (pinfunction "GND_G3") (pintype "bidirectional"))
      (node (ref "U$6") (pin "G4") (pinfunction "GND_G4") (pintype "bidirectional"))
      (node (ref "U$6") (pin "G5") (pinfunction "GND_G5") (pintype "bidirectional"))
      (node (ref "X3") (pin "7") (pinfunction "KL_7") (pintype "passive"))
    )
    (net (code "62") (name "Net-(X4A-KL)") (class "Default")
      (node (ref "C61") (pin "2") (pinfunction "2_2") (pintype "passive"))
      (node (ref "U$1") (pin "3") (pinfunction "3_3") (pintype "passive"))
      (node (ref "X4") (pin "1") (pinfunction "KL_1") (pintype "passive"))
    )
    (net (code "63") (name "Net-(X4C-KL)") (class "Default")
      (node (ref "F1") (pin "1") (pinfunction "1_1") (pintype "passive"))
      (node (ref "X4") (pin "3") (pinfunction "KL_3") (pintype "passive"))
    )
    (net (code "64") (name "Net-(X6B-KL)") (class "Default")
      (node (ref "C26") (pin "1") (pinfunction "1_1") (pintype "passive"))
      (node (ref "C28") (pin "2") (pinfunction "2_2") (pintype "passive"))
      (node (ref "D17") (pin "A") (pinfunction "A_A") (pintype "passive"))
      (node (ref "D19") (pin "C") (pinfunction "C_C") (pintype "passive"))
      (node (ref "X6") (pin "2") (pinfunction "KL_2") (pintype "passive"))
    )
    (net (code "65") (name "Net-(X7A-KL)") (class "Default")
      (node (ref "C25") (pin "1") (pinfunction "1_1") (pintype "passive"))
      (node (ref "C27") (pin "2") (pinfunction "2_2") (pintype "passive"))
      (node (ref "D16") (pin "A") (pinfunction "A_A") (pintype "passive"))
      (node (ref "D18") (pin "C") (pinfunction "C_C") (pintype "passive"))
      (node (ref "X7") (pin "1") (pinfunction "KL_1") (pintype "passive"))
    )
    (net (code "66") (name "Net-(X9A-KL)") (class "Default")
      (node (ref "C61") (pin "1") (pinfunction "1_1") (pintype "passive"))
      (node (ref "C66") (pin "2") (pinfunction "2_2") (pintype "passive"))
      (node (ref "U$1") (pin "1") (pinfunction "1_1") (pintype "passive"))
      (node (ref "X9") (pin "1") (pinfunction "KL_1") (pintype "passive"))
    )
    (net (code "67") (name "Net-(X9B-KL)") (class "Default")
      (node (ref "C66") (pin "1") (pinfunction "1_1") (pintype "passive"))
      (node (ref "F1") (pin "2") (pinfunction "2_2") (pintype "passive"))
      (node (ref "X9") (pin "2") (pinfunction "KL_2") (pintype "passive"))
    )
    (net (code "68") (name "Net-(X10A-KL)") (class "Default")
      (node (ref "C62") (pin "2") (pinfunction "2_2") (pintype "passive"))
      (node (ref "C63") (pin "2") (pinfunction "2_2") (pintype "passive"))
      (node (ref "X10") (pin "1") (pinfunction "KL_1") (pintype "passive"))
      (node (ref "X10") (pin "2") (pinfunction "KL_2") (pintype "passive"))
      (node (ref "X4") (pin "2") (pinfunction "KL_2") (pintype "passive"))
    )
    (net (code "69") (name "Net-(X11A-KL)") (class "Default")
      (node (ref "C64") (pin "1") (pinfunction "1_1") (pintype "passive"))
      (node (ref "U$2") (pin "2") (pinfunction "2_2") (pintype "passive"))
      (node (ref "X11") (pin "1") (pinfunction "KL_1") (pintype "passive"))
      (node (ref "X5") (pin "1") (pinfunction "KL_1") (pintype "passive"))
      (node (ref "X8") (pin "1") (pinfunction "KL_1") (pintype "passive"))
    )
    (net (code "70") (name "Net-(X11B-KL)") (class "Default")
      (node (ref "C64") (pin "2") (pinfunction "2_2") (pintype "passive"))
      (node (ref "U$2") (pin "4") (pinfunction "4_4") (pintype "passive"))
      (node (ref "X11") (pin "2") (pinfunction "KL_2") (pintype "passive"))
      (node (ref "X5") (pin "2") (pinfunction "KL_2") (pintype "passive"))
      (node (ref "X8") (pin "2") (pinfunction "KL_2") (pintype "passive"))
    )
    (net (code "71") (name "V+") (class "Default")
      (node (ref "C16") (pin "+") (pinfunction "+_+") (pintype "passive"))
      (node (ref "C20") (pin "2") (pinfunction "2_2") (pintype "passive"))
      (node (ref "C24") (pin "1") (pinfunction "1_1") (pintype "passive"))
      (node (ref "C38") (pin "2") (pinfunction "2_2") (pintype "passive"))
      (node (ref "C6") (pin "+") (pinfunction "+_+") (pintype "passive"))
      (node (ref "D11") (pin "A") (pinfunction "A_A") (pintype "passive"))
      (node (ref "IC1") (pin "7") (pinfunction "V+_7") (pintype "power_in"))
      (node (ref "Q7") (pin "3") (pinfunction "E_3") (pintype "passive"))
      (node (ref "Q8") (pin "1") (pinfunction "D_1") (pintype "passive"))
      (node (ref "R13") (pin "2") (pinfunction "2_2") (pintype "passive"))
      (node (ref "R8") (pin "2") (pinfunction "2_2") (pintype "passive"))
      (node (ref "X2") (pin "1") (pinfunction "KL_1") (pintype "passive"))
    )
    (net (code "72") (name "V-") (class "Default")
      (node (ref "C10") (pin "-") (pinfunction "-_-") (pintype "passive"))
      (node (ref "C19") (pin "1") (pinfunction "1_1") (pintype "passive"))
      (node (ref "C21") (pin "2") (pinfunction "2_2") (pintype "passive"))
      (node (ref "C3") (pin "-") (pinfunction "-_-") (pintype "passive"))
      (node (ref "C40") (pin "1") (pinfunction "1_1") (pintype "passive"))
      (node (ref "D10") (pin "C") (pinfunction "C_C") (pintype "passive"))
      (node (ref "IC2") (pin "4") (pinfunction "V-_4") (pintype "power_in"))
      (node (ref "Q12") (pin "2") (pinfunction "G_2") (pintype "passive"))
      (node (ref "Q4") (pin "3") (pinfunction "E_3") (pintype "passive"))
      (node (ref "R12") (pin "1") (pinfunction "1_1") (pintype "passive"))
      (node (ref "R14") (pin "1") (pinfunction "1_1") (pintype "passive"))
      (node (ref "R9") (pin "1") (pinfunction "1_1") (pintype "passive"))
      (node (ref "X2") (pin "3") (pinfunction "KL_3") (pintype "passive"))
    )
    (net (code "73") (name "unconnected-(IC1-TRIM1-Pad1)") (class "Default")
      (node (ref "IC1") (pin "1") (pinfunction "TRIM1_1") (pintype "passive"))
    )
    (net (code "74") (name "unconnected-(IC1-TRIM2-Pad8)") (class "Default")
      (node (ref "IC1") (pin "8") (pinfunction "TRIM2_8") (pintype "passive"))
    )
    (net (code "75") (name "unconnected-(IC2-TRIM1-Pad1)") (class "Default")
      (node (ref "IC2") (pin "1") (pinfunction "TRIM1_1") (pintype "passive"))
    )
    (net (code "76") (name "unconnected-(IC2-TRIM2-Pad8)") (class "Default")
      (node (ref "IC2") (pin "8") (pinfunction "TRIM2_8") (pintype "passive"))
    )
    (net (code "77") (name "unconnected-(KK5-K-PadK1)") (class "Default")
      (node (ref "KK5") (pin "K1") (pinfunction "K_K1") (pintype "passive"))
    )
    (net (code "78") (name "unconnected-(KK5-K-PadK2)") (class "Default")
      (node (ref "KK5") (pin "K2") (pinfunction "K_K2") (pintype "passive"))
    )
    (net (code "79") (name "unconnected-(KK6-K-PadK1)") (class "Default")
      (node (ref "KK6") (pin "K1") (pinfunction "K_K1") (pintype "passive"))
    )
    (net (code "80") (name "unconnected-(KK6-K-PadK2)") (class "Default")
      (node (ref "KK6") (pin "K2") (pinfunction "K_K2") (pintype "passive"))
    )
  )
)
